# xtal_2nd_mixer.net
KiCad netlist of a schematic drawn in EAGLE
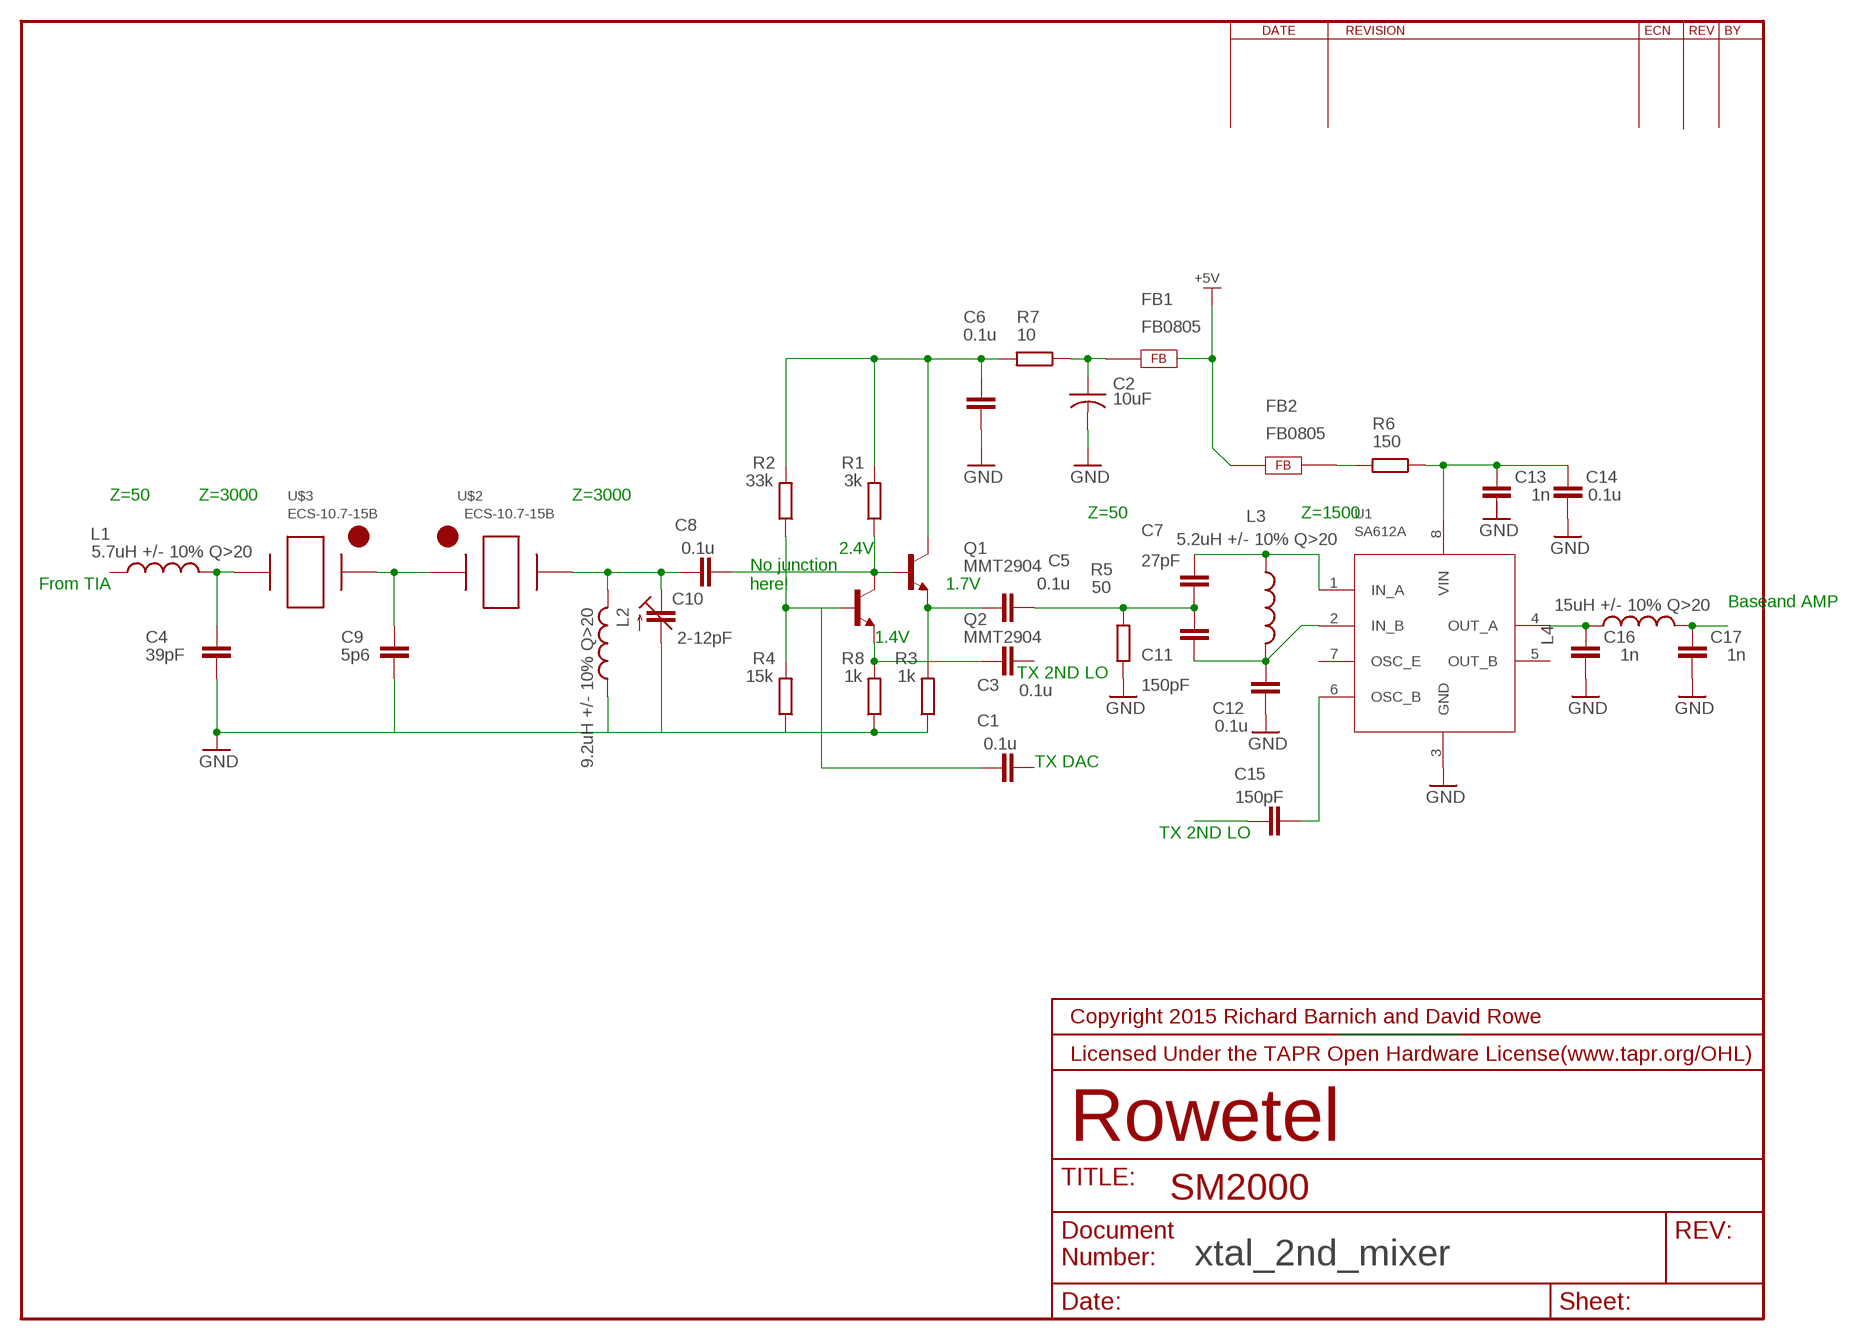
[diagram p0: schematic, sheet 1]

(export (version "E")
  (design (tool "Eeschema 10.0.6"))
  (components
    (comp (ref "C1")
      (value "0.1u")
      (footprint "eagle-import:C025-024X044")
      (libsource (lib "eagle-import") (part "C-EU025-024X044"))
    )
    (comp (ref "C2")
      (value "10uF")
      (footprint "eagle-import:C1210")
      (libsource (lib "eagle-import") (part "CAP-1210"))
    )
    (comp (ref "C3")
      (value "0.1u")
      (footprint "eagle-import:C025-024X044")
      (libsource (lib "eagle-import") (part "C-EU025-024X044"))
    )
    (comp (ref "C4")
      (value "39pF")
      (footprint "eagle-import:C025-024X044")
      (libsource (lib "eagle-import") (part "C-EU025-024X044"))
    )
    (comp (ref "C5")
      (value "0.1u")
      (footprint "eagle-import:C025-024X044")
      (libsource (lib "eagle-import") (part "C-EU025-024X044"))
    )
    (comp (ref "C6")
      (value "0.1u")
      (footprint "eagle-import:C025-024X044")
      (libsource (lib "eagle-import") (part "C-EU025-024X044"))
    )
    (comp (ref "C7")
      (value "27pF")
      (footprint "eagle-import:C025-024X044")
      (libsource (lib "eagle-import") (part "C-EU025-024X044"))
    )
    (comp (ref "C8")
      (value "0.1u")
      (footprint "eagle-import:C025-024X044")
      (libsource (lib "eagle-import") (part "C-EU025-024X044"))
    )
    (comp (ref "C9")
      (value "5p6")
      (footprint "eagle-import:C025-024X044")
      (libsource (lib "eagle-import") (part "C-EU025-024X044"))
    )
    (comp (ref "C10")
      (value "2-12pF")
      (footprint "eagle-import:3008")
      (libsource (lib "eagle-import") (part "C-TRIMM3008"))
    )
    (comp (ref "C11")
      (value "150pF")
      (footprint "eagle-import:C025-024X044")
      (libsource (lib "eagle-import") (part "C-EU025-024X044"))
    )
    (comp (ref "C12")
      (value "0.1u")
      (footprint "eagle-import:C025-024X044")
      (libsource (lib "eagle-import") (part "C-EU025-024X044"))
    )
    (comp (ref "C13")
      (value "1n")
      (footprint "eagle-import:C025-024X044")
      (libsource (lib "eagle-import") (part "C-EU025-024X044"))
    )
    (comp (ref "C14")
      (value "0.1u")
      (footprint "eagle-import:C025-024X044")
      (libsource (lib "eagle-import") (part "C-EU025-024X044"))
    )
    (comp (ref "C15")
      (value "150pF")
      (footprint "eagle-import:C025-024X044")
      (libsource (lib "eagle-import") (part "C-EU025-024X044"))
    )
    (comp (ref "C16")
      (value "1n")
      (footprint "eagle-import:C025-024X044")
      (libsource (lib "eagle-import") (part "C-EU025-024X044"))
    )
    (comp (ref "C17")
      (value "1n")
      (footprint "eagle-import:C025-024X044")
      (libsource (lib "eagle-import") (part "C-EU025-024X044"))
    )
    (comp (ref "FB1")
      (value "FB0805")
      (footprint "eagle-import:FE0805")
      (libsource (lib "eagle-import") (part "FB0805"))
    )
    (comp (ref "FB2")
      (value "FB0805")
      (footprint "eagle-import:FE0805")
      (libsource (lib "eagle-import") (part "FB0805"))
    )
    (comp (ref "L1")
      (value "5.7uH +/- 10% Q>20")
      (footprint "eagle-import:0204_5")
      (libsource (lib "eagle-import") (part "L-US0204/5"))
    )
    (comp (ref "L2")
      (value "9.2uH +/- 10% Q>20")
      (footprint "eagle-import:0204_5")
      (libsource (lib "eagle-import") (part "L-US0204/5"))
    )
    (comp (ref "L3")
      (value "5.2uH +/- 10% Q>20")
      (footprint "eagle-import:0204_5")
      (libsource (lib "eagle-import") (part "L-US0204/5"))
    )
    (comp (ref "L4")
      (value "15uH +/- 10% Q>20")
      (footprint "eagle-import:0204_5")
      (libsource (lib "eagle-import") (part "L-US0204/5"))
    )
    (comp (ref "Q1")
      (value "MMT2904")
      (footprint "eagle-import:SOT23-EBC")
      (libsource (lib "eagle-import") (part "-NPN-SOT23-EBC"))
    )
    (comp (ref "Q2")
      (value "MMT2904")
      (footprint "eagle-import:SOT23-EBC")
      (libsource (lib "eagle-import") (part "-NPN-SOT23-EBC"))
    )
    (comp (ref "R1")
      (value "3k")
      (footprint "eagle-import:RESC2012X70N")
      (libsource (lib "eagle-import") (part "RESISTOR_0805"))
    )
    (comp (ref "R2")
      (value "33k")
      (footprint "eagle-import:RESC2012X70N")
      (libsource (lib "eagle-import") (part "RESISTOR_0805"))
    )
    (comp (ref "R3")
      (value "1k")
      (footprint "eagle-import:RESC2012X70N")
      (libsource (lib "eagle-import") (part "RESISTOR_0805"))
    )
    (comp (ref "R4")
      (value "15k")
      (footprint "eagle-import:RESC2012X70N")
      (libsource (lib "eagle-import") (part "RESISTOR_0805"))
    )
    (comp (ref "R5")
      (value "50")
      (footprint "eagle-import:RESC2012X70N")
      (libsource (lib "eagle-import") (part "RESISTOR_0805"))
    )
    (comp (ref "R6")
      (value "150")
      (footprint "eagle-import:RESC2012X70N")
      (libsource (lib "eagle-import") (part "RESISTOR_0805"))
    )
    (comp (ref "R7")
      (value "10")
      (footprint "eagle-import:RESC2012X70N")
      (libsource (lib "eagle-import") (part "RESISTOR_0805"))
    )
    (comp (ref "R8")
      (value "1k")
      (footprint "eagle-import:RESC2012X70N")
      (libsource (lib "eagle-import") (part "RESISTOR_0805"))
    )
    (comp (ref "U$2")
      (value "ECS-10.7-15B")
      (footprint "eagle-import:HC49_S")
      (libsource (lib "eagle-import") (part "ECS-10.7-15B"))
    )
    (comp (ref "U$3")
      (value "ECS-10.7-15B")
      (footprint "eagle-import:HC49_S")
      (libsource (lib "eagle-import") (part "ECS-10.7-15B"))
    )
    (comp (ref "U1")
      (value "SA612A")
      (footprint "eagle-import:SO-08")
      (libsource (lib "eagle-import") (part "SA612A"))
    )
  )
  (nets
    (net (code "1") (name "+5V") (class "Default")
      (node (ref "FB1") (pin "2") (pinfunction "2_2") (pintype "passive"))
      (node (ref "FB2") (pin "1") (pinfunction "1_1") (pintype "passive"))
    )
    (net (code "2") (name "GND") (class "Default")
      (node (ref "C10") (pin "-") (pinfunction "A_-") (pintype "passive"))
      (node (ref "C12") (pin "1") (pinfunction "1_1") (pintype "passive"))
      (node (ref "C14") (pin "1") (pinfunction "1_1") (pintype "passive"))
      (node (ref "C16") (pin "1") (pinfunction "1_1") (pintype "passive"))
      (node (ref "C17") (pin "1") (pinfunction "1_1") (pintype "passive"))
      (node (ref "C2") (pin "2") (pinfunction "2_2") (pintype "passive"))
      (node (ref "C4") (pin "2") (pinfunction "2_2") (pintype "passive"))
      (node (ref "C6") (pin "2") (pinfunction "2_2") (pintype "passive"))
      (node (ref "C9") (pin "2") (pinfunction "2_2") (pintype "passive"))
      (node (ref "L2") (pin "1") (pinfunction "1_1") (pintype "passive"))
      (node (ref "R3") (pin "1") (pinfunction "1_1") (pintype "passive"))
      (node (ref "R5") (pin "1") (pinfunction "1_1") (pintype "passive"))
      (node (ref "R8") (pin "1") (pinfunction "1_1") (pintype "passive"))
      (node (ref "U1") (pin "3") (pinfunction "GND_3") (pintype "bidirectional"))
    )
    (net (code "3") (name "Net-(C1-Pad1)") (class "Default")
      (node (ref "C1") (pin "1") (pinfunction "1_1") (pintype "passive"))
      (node (ref "Q2") (pin "B") (pinfunction "B_B") (pintype "passive"))
      (node (ref "R2") (pin "1") (pinfunction "1_1") (pintype "passive"))
      (node (ref "R4") (pin "2") (pinfunction "2_2") (pintype "passive"))
    )
    (net (code "4") (name "Net-(C2-Pad1)") (class "Default")
      (node (ref "C2") (pin "1") (pinfunction "1_1") (pintype "passive"))
      (node (ref "FB1") (pin "1") (pinfunction "1_1") (pintype "passive"))
      (node (ref "R7") (pin "1") (pinfunction "1_1") (pintype "passive"))
    )
    (net (code "5") (name "Net-(C3-Pad1)") (class "Default")
      (node (ref "C3") (pin "1") (pinfunction "1_1") (pintype "passive"))
      (node (ref "Q2") (pin "E") (pinfunction "E_E") (pintype "passive"))
      (node (ref "R8") (pin "2") (pinfunction "2_2") (pintype "passive"))
    )
    (net (code "6") (name "Net-(C4-Pad1)") (class "Default")
      (node (ref "C4") (pin "1") (pinfunction "1_1") (pintype "passive"))
      (node (ref "L1") (pin "2") (pinfunction "2_2") (pintype "passive"))
      (node (ref "U$3") (pin "1") (pinfunction "1_1") (pintype "bidirectional"))
    )
    (net (code "7") (name "Net-(C5-Pad1)") (class "Default")
      (node (ref "C5") (pin "1") (pinfunction "1_1") (pintype "passive"))
      (node (ref "Q1") (pin "E") (pinfunction "E_E") (pintype "passive"))
      (node (ref "R3") (pin "2") (pinfunction "2_2") (pintype "passive"))
    )
    (net (code "8") (name "Net-(C6-Pad1)") (class "Default")
      (node (ref "C6") (pin "1") (pinfunction "1_1") (pintype "passive"))
      (node (ref "Q1") (pin "C") (pinfunction "C_C") (pintype "passive"))
      (node (ref "R1") (pin "2") (pinfunction "2_2") (pintype "passive"))
      (node (ref "R2") (pin "2") (pinfunction "2_2") (pintype "passive"))
      (node (ref "R7") (pin "2") (pinfunction "2_2") (pintype "passive"))
    )
    (net (code "9") (name "Net-(C8-Pad2)") (class "Default")
      (node (ref "C8") (pin "2") (pinfunction "2_2") (pintype "passive"))
      (node (ref "Q1") (pin "B") (pinfunction "B_B") (pintype "passive"))
      (node (ref "Q2") (pin "C") (pinfunction "C_C") (pintype "passive"))
      (node (ref "R1") (pin "1") (pinfunction "1_1") (pintype "passive"))
    )
    (net (code "10") (name "Net-(C9-Pad1)") (class "Default")
      (node (ref "C9") (pin "1") (pinfunction "1_1") (pintype "passive"))
      (node (ref "U$2") (pin "2") (pinfunction "2_2") (pintype "bidirectional"))
      (node (ref "U$3") (pin "2") (pinfunction "2_2") (pintype "bidirectional"))
    )
    (net (code "11") (name "Net-(C10-E)") (class "Default")
      (node (ref "C10") (pin "+") (pinfunction "E_+") (pintype "passive"))
      (node (ref "C8") (pin "1") (pinfunction "1_1") (pintype "passive"))
      (node (ref "L2") (pin "2") (pinfunction "2_2") (pintype "passive"))
      (node (ref "U$2") (pin "1") (pinfunction "1_1") (pintype "bidirectional"))
    )
    (net (code "12") (name "Net-(C11-Pad2)") (class "Default")
      (node (ref "C11") (pin "2") (pinfunction "2_2") (pintype "passive"))
      (node (ref "C5") (pin "2") (pinfunction "2_2") (pintype "passive"))
      (node (ref "C7") (pin "1") (pinfunction "1_1") (pintype "passive"))
      (node (ref "R5") (pin "2") (pinfunction "2_2") (pintype "passive"))
    )
    (net (code "13") (name "Net-(C17-Pad2)") (class "Default")
      (node (ref "C17") (pin "2") (pinfunction "2_2") (pintype "passive"))
      (node (ref "L4") (pin "2") (pinfunction "2_2") (pintype "passive"))
    )
    (net (code "14") (name "Net-(FB2-Pad2)") (class "Default")
      (node (ref "FB2") (pin "2") (pinfunction "2_2") (pintype "passive"))
      (node (ref "R6") (pin "2") (pinfunction "2_2") (pintype "passive"))
    )
    (net (code "15") (name "Net-(U1-IN_A)") (class "Default")
      (node (ref "C7") (pin "2") (pinfunction "2_2") (pintype "passive"))
      (node (ref "L3") (pin "1") (pinfunction "1_1") (pintype "passive"))
      (node (ref "U1") (pin "1") (pinfunction "IN_A_1") (pintype "bidirectional"))
    )
    (net (code "16") (name "Net-(U1-IN_B)") (class "Default")
      (node (ref "C11") (pin "1") (pinfunction "1_1") (pintype "passive"))
      (node (ref "C12") (pin "2") (pinfunction "2_2") (pintype "passive"))
      (node (ref "L3") (pin "2") (pinfunction "2_2") (pintype "passive"))
      (node (ref "U1") (pin "2") (pinfunction "IN_B_2") (pintype "bidirectional"))
    )
    (net (code "17") (name "Net-(U1-OSC_B)") (class "Default")
      (node (ref "C15") (pin "2") (pinfunction "2_2") (pintype "passive"))
      (node (ref "U1") (pin "6") (pinfunction "OSC_B_6") (pintype "bidirectional"))
    )
    (net (code "18") (name "Net-(U1-OUT_A)") (class "Default")
      (node (ref "C16") (pin "2") (pinfunction "2_2") (pintype "passive"))
      (node (ref "L4") (pin "1") (pinfunction "1_1") (pintype "passive"))
      (node (ref "U1") (pin "4") (pinfunction "OUT_A_4") (pintype "bidirectional"))
    )
    (net (code "19") (name "Net-(U1-VIN)") (class "Default")
      (node (ref "C13") (pin "2") (pinfunction "2_2") (pintype "passive"))
      (node (ref "C14") (pin "2") (pinfunction "2_2") (pintype "passive"))
      (node (ref "R6") (pin "1") (pinfunction "1_1") (pintype "passive"))
      (node (ref "U1") (pin "8") (pinfunction "VIN_8") (pintype "bidirectional"))
    )
    (net (code "20") (name "unconnected-(C1-Pad2)") (class "Default")
      (node (ref "C1") (pin "2") (pinfunction "2_2") (pintype "passive"))
    )
    (net (code "21") (name "unconnected-(C3-Pad2)") (class "Default")
      (node (ref "C3") (pin "2") (pinfunction "2_2") (pintype "passive"))
    )
    (net (code "22") (name "unconnected-(C13-Pad1)") (class "Default")
      (node (ref "C13") (pin "1") (pinfunction "1_1") (pintype "passive"))
    )
    (net (code "23") (name "unconnected-(C15-Pad1)") (class "Default")
      (node (ref "C15") (pin "1") (pinfunction "1_1") (pintype "passive"))
    )
    (net (code "24") (name "unconnected-(L1-Pad1)") (class "Default")
      (node (ref "L1") (pin "1") (pinfunction "1_1") (pintype "passive"))
    )
    (net (code "25") (name "unconnected-(R4-Pad1)") (class "Default")
      (node (ref "R4") (pin "1") (pinfunction "1_1") (pintype "passive"))
    )
    (net (code "26") (name "unconnected-(U1-OSC_E-Pad7)") (class "Default")
      (node (ref "U1") (pin "7") (pinfunction "OSC_E_7") (pintype "bidirectional"))
    )
    (net (code "27") (name "unconnected-(U1-OUT_B-Pad5)") (class "Default")
      (node (ref "U1") (pin "5") (pinfunction "OUT_B_5") (pintype "bidirectional"))
    )
  )
)
